# 2019.net
KiCad netlist of a schematic drawn in EAGLE
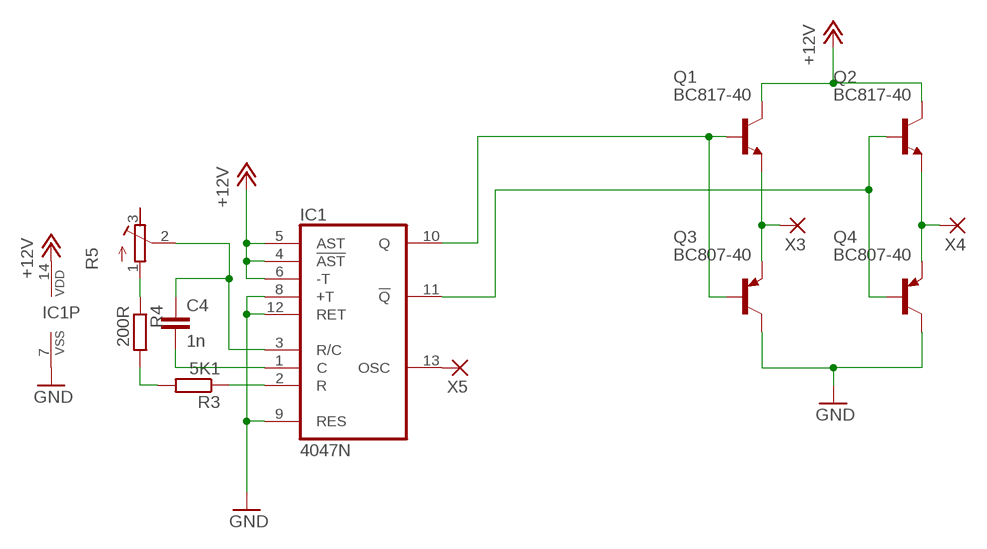
[diagram p0: schematic, sheet 1]
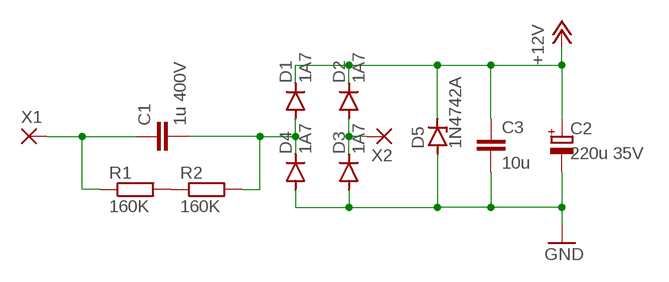
[diagram p1: schematic, sheet 2]

(export (version "E")
  (design (tool "Eeschema 10.0.6"))
  (components
    (comp (ref "C4")
      (value "1n")
      (footprint "eagle-import:CAP0805")
      (libsource (lib "eagle-import") (part "CAP_0805"))
    )
    (comp (ref "IC1")
      (value "4047N")
      (footprint "eagle-import:DIL14")
      (libsource (lib "eagle-import") (part "4047N"))
    )
    (comp (ref "Q1")
      (value "BC817-40")
      (footprint "eagle-import:SOT95P240X115-3")
      (libsource (lib "eagle-import") (part "TRANS-NPNSOT-23"))
    )
    (comp (ref "Q2")
      (value "BC817-40")
      (footprint "eagle-import:SOT95P240X115-3")
      (libsource (lib "eagle-import") (part "TRANS-NPNSOT-23"))
    )
    (comp (ref "Q3")
      (value "BC807-40")
      (footprint "eagle-import:SOT95P240X115-3")
      (libsource (lib "eagle-import") (part "TRANS-PNPSOT-23"))
    )
    (comp (ref "Q4")
      (value "BC807-40")
      (footprint "eagle-import:SOT95P240X115-3")
      (libsource (lib "eagle-import") (part "TRANS-PNPSOT-23"))
    )
    (comp (ref "R3")
      (value "5K1")
      (footprint "eagle-import:RESC2012X50")
      (libsource (lib "eagle-import") (part "R_R0805"))
    )
    (comp (ref "R4")
      (value "200R")
      (footprint "eagle-import:RESC2012X50")
      (libsource (lib "eagle-import") (part "R_R0805"))
    )
    (comp (ref "R5")
      (value "R_POT3296X")
      (footprint "eagle-import:POT-3296X")
      (libsource (lib "eagle-import") (part "R_POT3296X"))
    )
    (comp (ref "X3")
      (value "WIREPAD-SMD2")
      (footprint "eagle-import:PAD-1.27X2.54")
      (libsource (lib "eagle-import") (part "WIREPAD-SMD2"))
    )
    (comp (ref "X4")
      (value "WIREPAD-SMD2")
      (footprint "eagle-import:PAD-1.27X2.54")
      (libsource (lib "eagle-import") (part "WIREPAD-SMD2"))
    )
    (comp (ref "X5")
      (value "WIREPAD-SMD2")
      (footprint "eagle-import:PAD-1.27X2.54")
      (libsource (lib "eagle-import") (part "WIREPAD-SMD2"))
    )
    (comp (ref "C1")
      (value "1u 400V")
      (footprint "eagle-import:C225-108X268")
      (libsource (lib "eagle-import") (part "C-EU225-108X268"))
    )
    (comp (ref "C2")
      (value "220u 35V")
      (footprint "eagle-import:E2,5-7")
      (libsource (lib "eagle-import") (part "CAP-POL_E2.5-7"))
    )
    (comp (ref "C3")
      (value "10u")
      (footprint "eagle-import:CAP1210")
      (libsource (lib "eagle-import") (part "CAP_1210"))
    )
    (comp (ref "D1")
      (value "1A7")
      (footprint "eagle-import:D-5")
      (libsource (lib "eagle-import") (part "DIODE-D-5"))
    )
    (comp (ref "D2")
      (value "1A7")
      (footprint "eagle-import:D-5")
      (libsource (lib "eagle-import") (part "DIODE-D-5"))
    )
    (comp (ref "D3")
      (value "1A7")
      (footprint "eagle-import:D-5")
      (libsource (lib "eagle-import") (part "DIODE-D-5"))
    )
    (comp (ref "D4")
      (value "1A7")
      (footprint "eagle-import:D-5")
      (libsource (lib "eagle-import") (part "DIODE-D-5"))
    )
    (comp (ref "D5")
      (value "1N4742A")
      (footprint "eagle-import:DO41Z10")
      (libsource (lib "eagle-import") (part "ZENER-DIODEDO41Z10"))
    )
    (comp (ref "R1")
      (value "160K")
      (footprint "eagle-import:MF-0125")
      (libsource (lib "eagle-import") (part "R_MF-0125"))
    )
    (comp (ref "R2")
      (value "160K")
      (footprint "eagle-import:MF-0125")
      (libsource (lib "eagle-import") (part "R_MF-0125"))
    )
    (comp (ref "X1")
      (value "WIREPAD-SMD2")
      (footprint "eagle-import:PAD-1.27X2.54")
      (libsource (lib "eagle-import") (part "WIREPAD-SMD2"))
    )
    (comp (ref "X2")
      (value "WIREPAD-SMD2")
      (footprint "eagle-import:PAD-1.27X2.54")
      (libsource (lib "eagle-import") (part "WIREPAD-SMD2"))
    )
  )
  (nets
    (net (code "1") (name "+12V") (class "Default")
      (node (ref "C2") (pin "+") (pinfunction "+_+") (pintype "passive"))
      (node (ref "C3") (pin "1") (pinfunction "1_1") (pintype "passive"))
      (node (ref "D1") (pin "C") (pinfunction "C_C") (pintype "passive"))
      (node (ref "D2") (pin "C") (pinfunction "C_C") (pintype "passive"))
      (node (ref "D5") (pin "C") (pinfunction "C_C") (pintype "passive"))
      (node (ref "IC1") (pin "14") (pinfunction "VDD_14") (pintype "power_in"))
      (node (ref "IC1") (pin "4") (pinfunction "~{AST}_4") (pintype "input"))
      (node (ref "IC1") (pin "5") (pinfunction "AST_5") (pintype "input"))
      (node (ref "IC1") (pin "6") (pinfunction "-T_6") (pintype "input"))
      (node (ref "Q1") (pin "3") (pinfunction "C_3") (pintype "passive"))
      (node (ref "Q2") (pin "3") (pinfunction "C_3") (pintype "passive"))
    )
    (net (code "2") (name "GND") (class "Default")
      (node (ref "C2") (pin "-") (pinfunction "-_-") (pintype "passive"))
      (node (ref "C3") (pin "2") (pinfunction "2_2") (pintype "passive"))
      (node (ref "D3") (pin "A") (pinfunction "A_A") (pintype "passive"))
      (node (ref "D4") (pin "A") (pinfunction "A_A") (pintype "passive"))
      (node (ref "D5") (pin "A") (pinfunction "A_A") (pintype "passive"))
      (node (ref "IC1") (pin "12") (pinfunction "RET_12") (pintype "input"))
      (node (ref "IC1") (pin "7") (pinfunction "VSS_7") (pintype "power_in"))
      (node (ref "IC1") (pin "8") (pinfunction "+T_8") (pintype "input"))
      (node (ref "IC1") (pin "9") (pinfunction "RES_9") (pintype "input"))
      (node (ref "Q3") (pin "3") (pinfunction "C_3") (pintype "passive"))
      (node (ref "Q4") (pin "3") (pinfunction "C_3") (pintype "passive"))
    )
    (net (code "3") (name "Net-(C1-Pad2)") (class "Default")
      (node (ref "C1") (pin "2") (pinfunction "2_2") (pintype "passive"))
      (node (ref "D1") (pin "A") (pinfunction "A_A") (pintype "passive"))
      (node (ref "D4") (pin "C") (pinfunction "C_C") (pintype "passive"))
      (node (ref "R2") (pin "2") (pinfunction "2_2") (pintype "passive"))
    )
    (net (code "4") (name "Net-(IC1A-C)") (class "Default")
      (node (ref "C4") (pin "2") (pinfunction "2_2") (pintype "passive"))
      (node (ref "IC1") (pin "1") (pinfunction "C_1") (pintype "input"))
    )
    (net (code "5") (name "Net-(IC1A-OSC)") (class "Default")
      (node (ref "IC1") (pin "13") (pinfunction "OSC_13") (pintype "output"))
      (node (ref "X5") (pin "P$1") (pinfunction "P_P$1") (pintype "passive"))
    )
    (net (code "6") (name "Net-(IC1A-Q)") (class "Default")
      (node (ref "IC1") (pin "10") (pinfunction "Q_10") (pintype "output"))
      (node (ref "Q1") (pin "1") (pinfunction "B_1") (pintype "passive"))
      (node (ref "Q3") (pin "1") (pinfunction "B_1") (pintype "passive"))
    )
    (net (code "7") (name "Net-(IC1A-R)") (class "Default")
      (node (ref "IC1") (pin "2") (pinfunction "R_2") (pintype "input"))
      (node (ref "R3") (pin "1") (pinfunction "1_1") (pintype "passive"))
    )
    (net (code "8") (name "Net-(IC1A-R{slash}C)") (class "Default")
      (node (ref "C4") (pin "1") (pinfunction "1_1") (pintype "passive"))
      (node (ref "IC1") (pin "3") (pinfunction "R/C_3") (pintype "input"))
      (node (ref "R5") (pin "2") (pinfunction "S_2") (pintype "passive"))
    )
    (net (code "9") (name "Net-(IC1A-~{Q})") (class "Default")
      (node (ref "IC1") (pin "11") (pinfunction "~{Q}_11") (pintype "output"))
      (node (ref "Q2") (pin "1") (pinfunction "B_1") (pintype "passive"))
      (node (ref "Q4") (pin "1") (pinfunction "B_1") (pintype "passive"))
    )
    (net (code "10") (name "Net-(Q1-E)") (class "Default")
      (node (ref "Q1") (pin "2") (pinfunction "E_2") (pintype "passive"))
      (node (ref "Q3") (pin "2") (pinfunction "E_2") (pintype "passive"))
      (node (ref "X3") (pin "P$1") (pinfunction "P_P$1") (pintype "passive"))
    )
    (net (code "11") (name "Net-(Q2-E)") (class "Default")
      (node (ref "Q2") (pin "2") (pinfunction "E_2") (pintype "passive"))
      (node (ref "Q4") (pin "2") (pinfunction "E_2") (pintype "passive"))
      (node (ref "X4") (pin "P$1") (pinfunction "P_P$1") (pintype "passive"))
    )
    (net (code "12") (name "Net-(R1-Pad2)") (class "Default")
      (node (ref "R1") (pin "2") (pinfunction "2_2") (pintype "passive"))
      (node (ref "R2") (pin "1") (pinfunction "1_1") (pintype "passive"))
    )
    (net (code "13") (name "Net-(R3-Pad2)") (class "Default")
      (node (ref "R3") (pin "2") (pinfunction "2_2") (pintype "passive"))
      (node (ref "R4") (pin "2") (pinfunction "2_2") (pintype "passive"))
    )
    (net (code "14") (name "Net-(R5-A)") (class "Default")
      (node (ref "R4") (pin "1") (pinfunction "1_1") (pintype "passive"))
      (node (ref "R5") (pin "1") (pinfunction "A_1") (pintype "passive"))
    )
    (net (code "15") (name "Net-(X1-P)") (class "Default")
      (node (ref "C1") (pin "1") (pinfunction "1_1") (pintype "passive"))
      (node (ref "R1") (pin "1") (pinfunction "1_1") (pintype "passive"))
      (node (ref "X1") (pin "P$1") (pinfunction "P_P$1") (pintype "passive"))
    )
    (net (code "16") (name "Net-(X2-P)") (class "Default")
      (node (ref "D2") (pin "A") (pinfunction "A_A") (pintype "passive"))
      (node (ref "D3") (pin "C") (pinfunction "C_C") (pintype "passive"))
      (node (ref "X2") (pin "P$1") (pinfunction "P_P$1") (pintype "passive"))
    )
    (net (code "17") (name "unconnected-(R5-E-Pad3)") (class "Default")
      (node (ref "R5") (pin "3") (pinfunction "E_3") (pintype "passive"))
    )
  )
)
